# moire_v1_2_plc.net
KiCad netlist of a schematic drawn in EAGLE
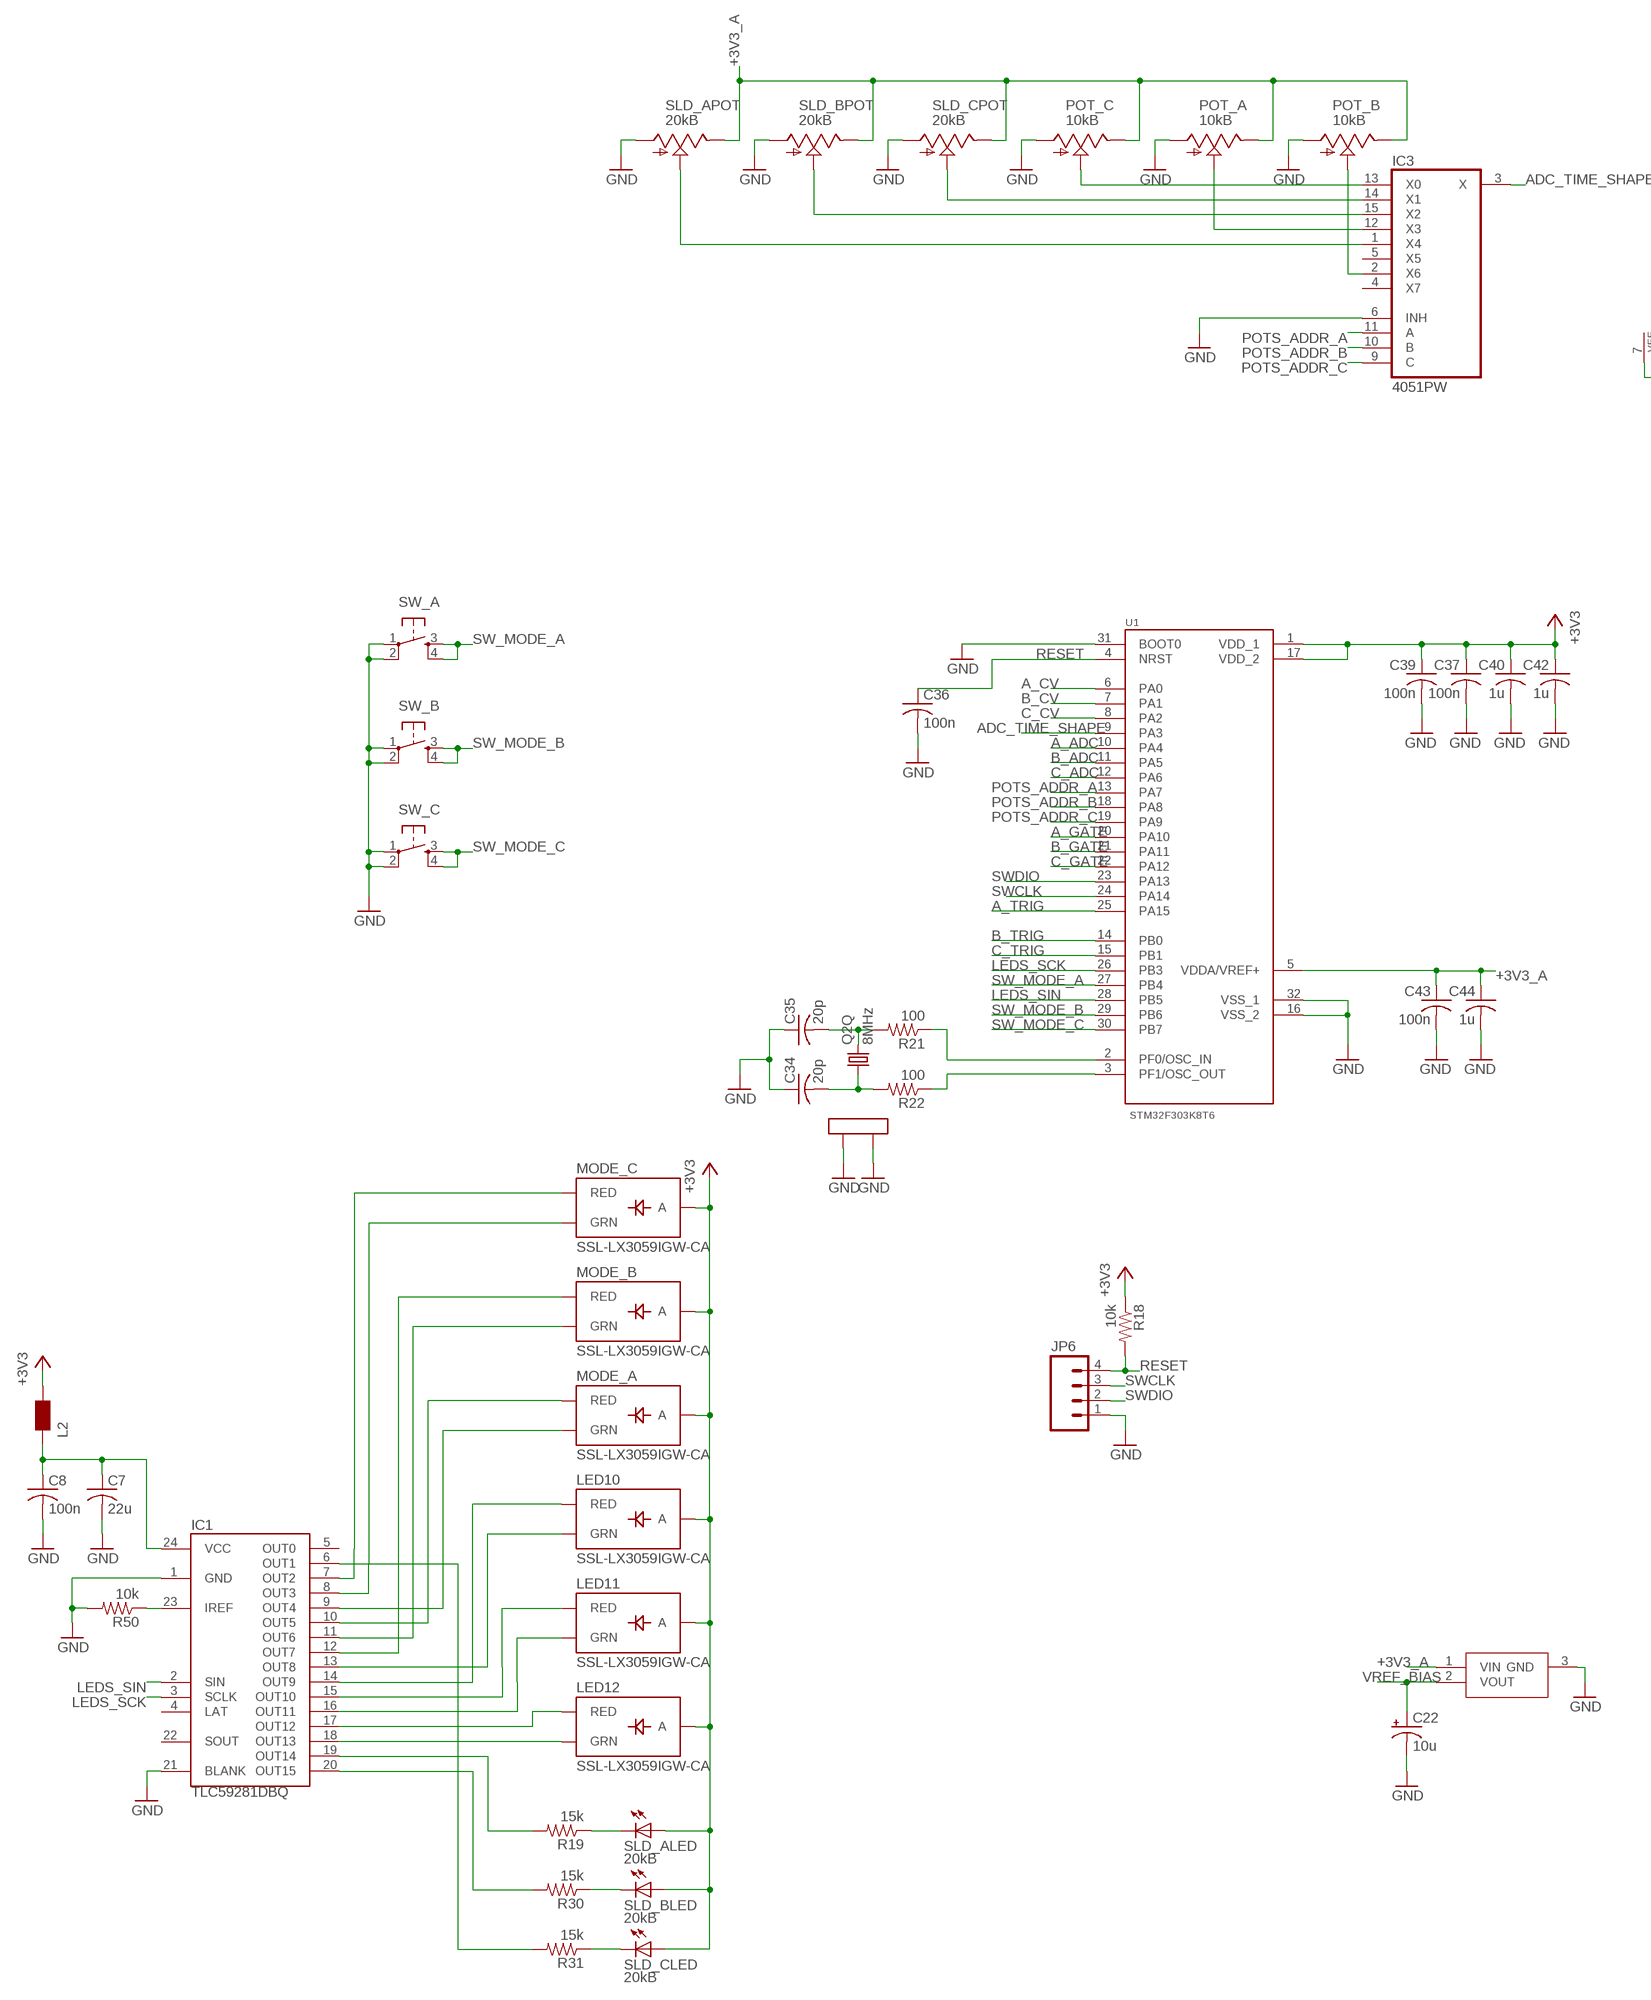
[diagram p0: schematic, sheet 1, part 1 of 2]
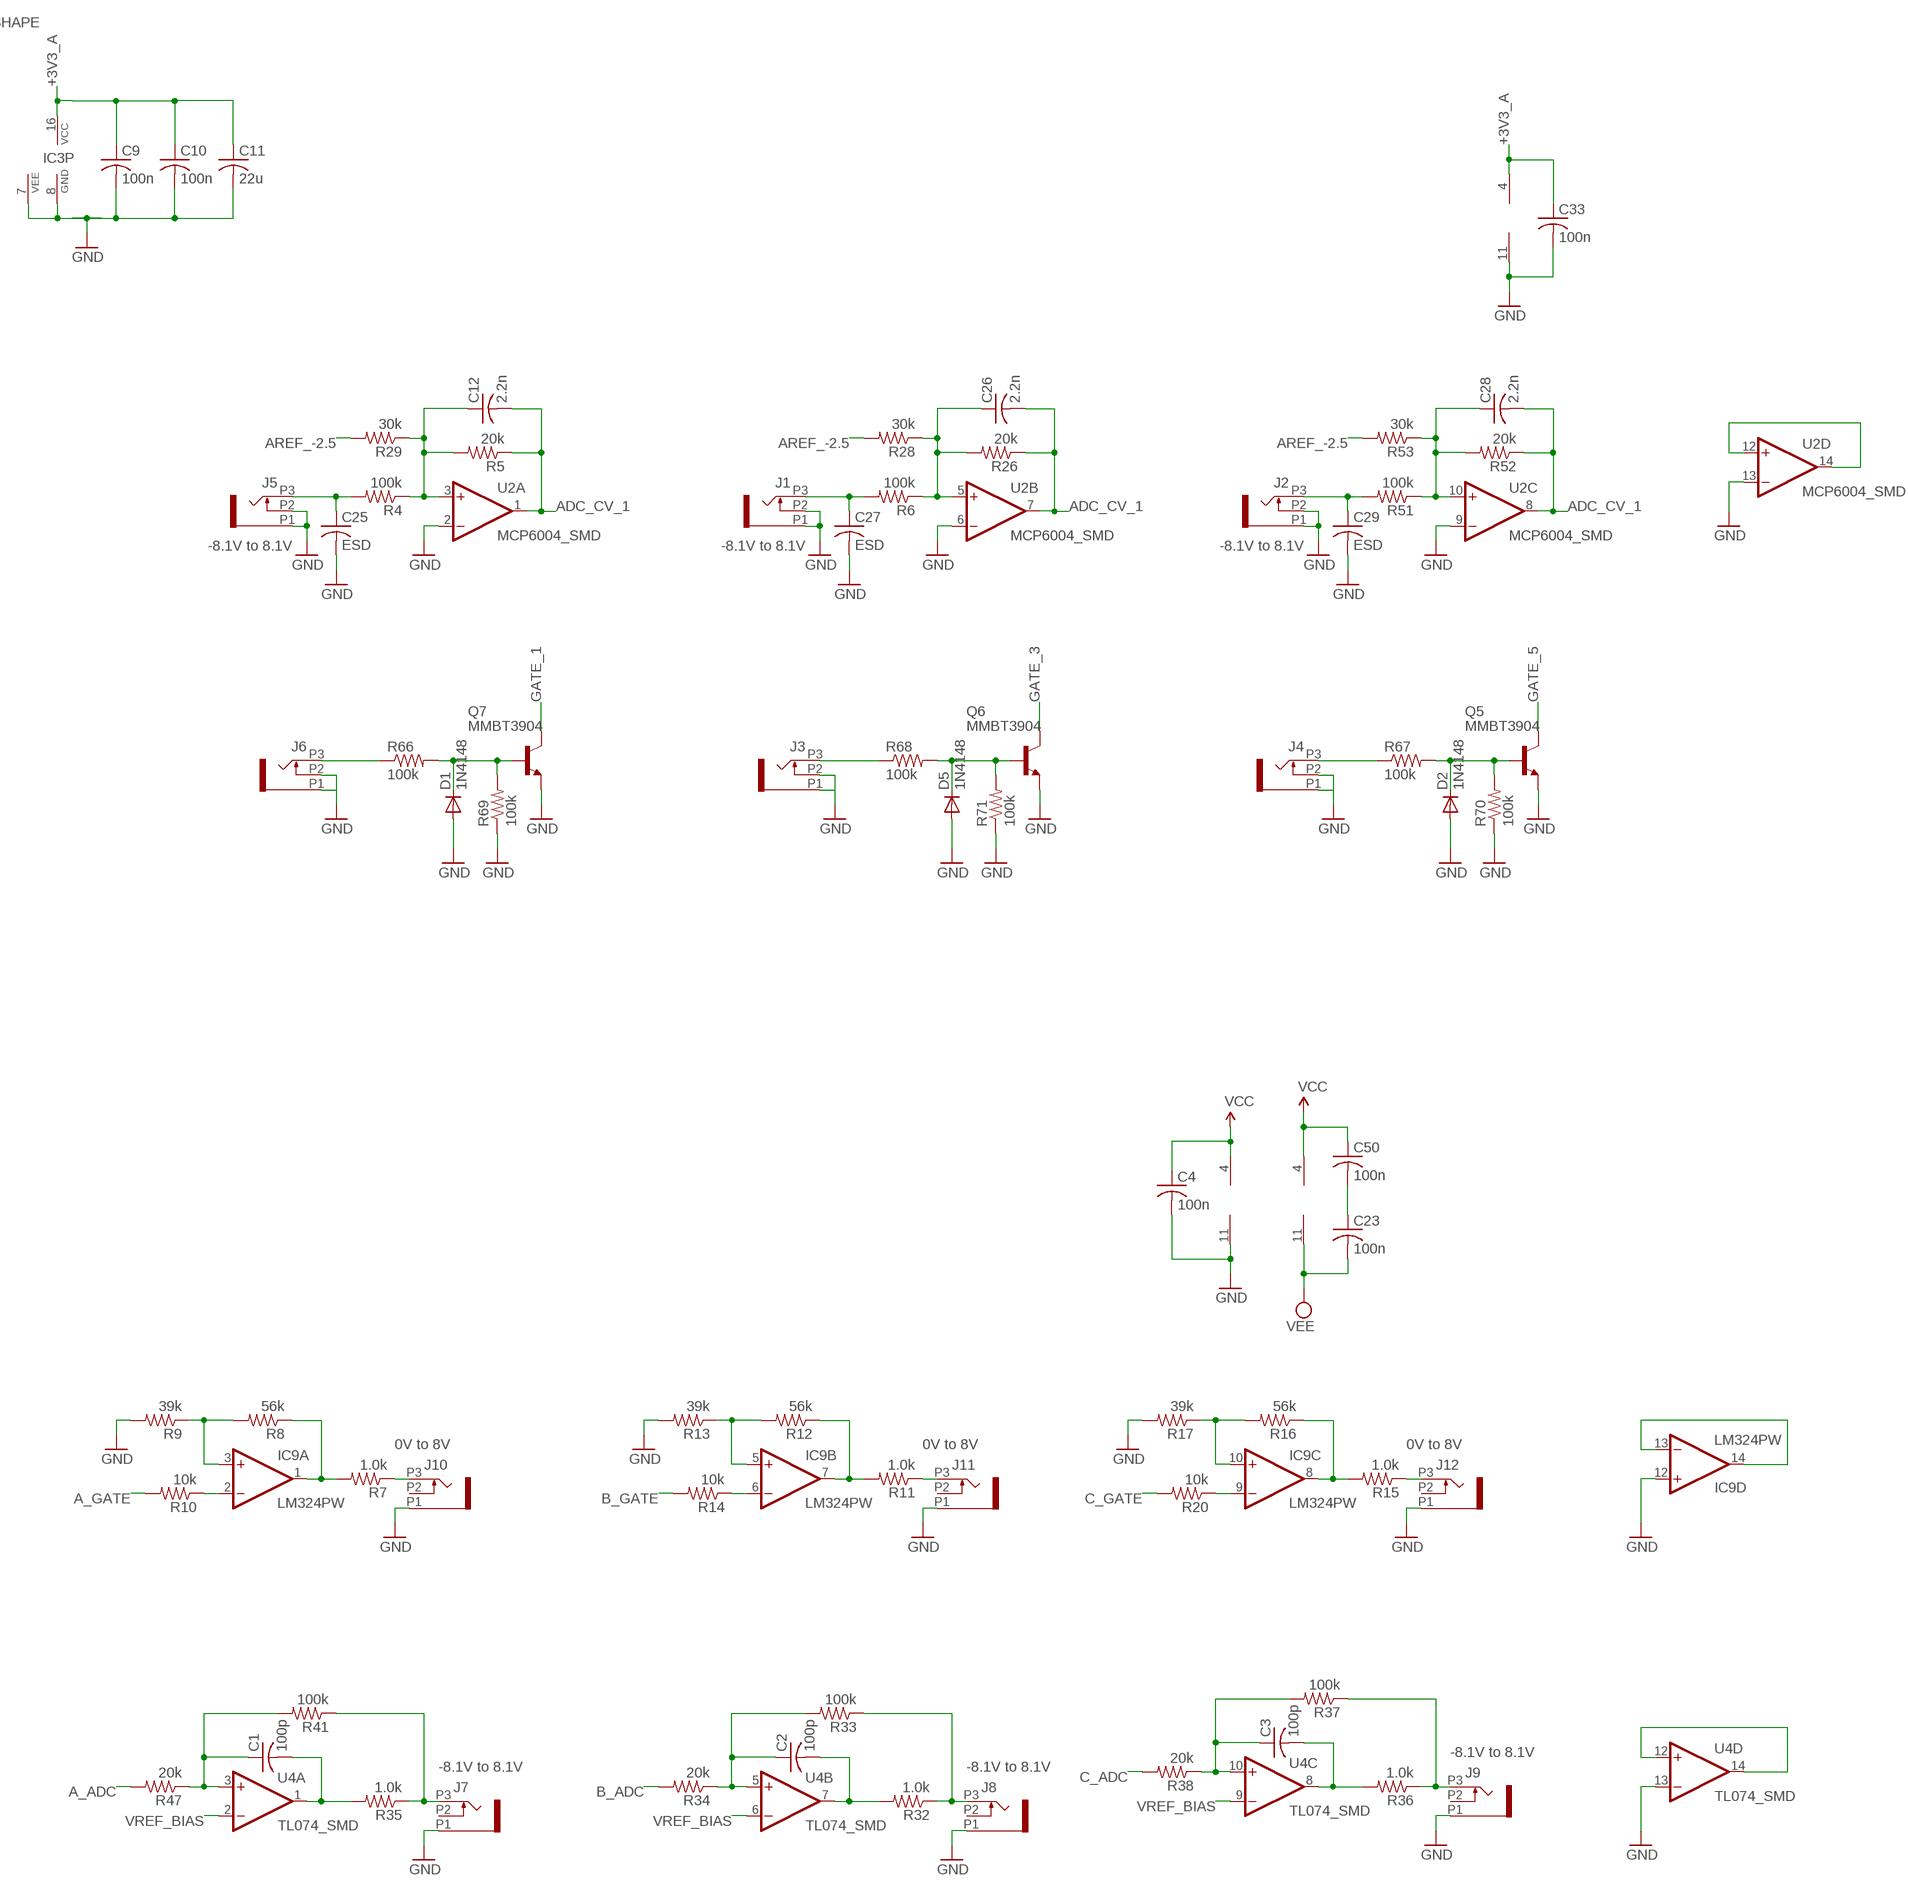
[diagram p1: schematic, sheet 1, part 2 of 2]
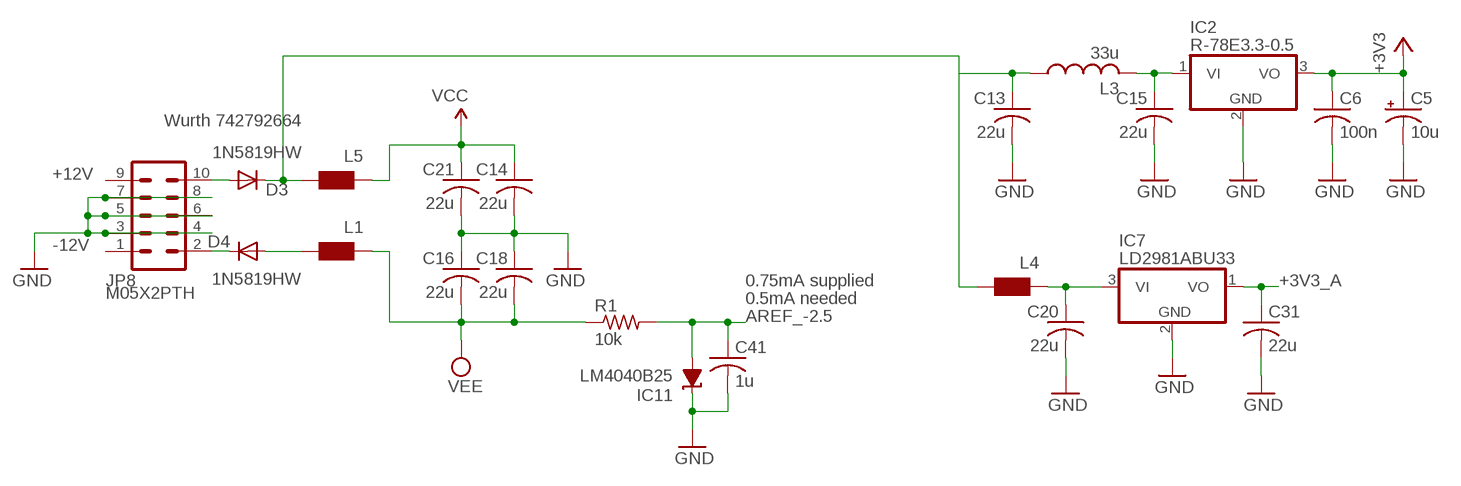
[diagram p2: schematic, sheet 2]

(export (version "E")
  (design (tool "Eeschema 10.0.6"))
  (components
    (comp (ref "C5")
      (value "10u")
      (footprint "eagle-import:PANASONIC_A")
      (libsource (lib "eagle-import") (part "CPOL-USA"))
    )
    (comp (ref "C6")
      (value "100n")
      (footprint "eagle-import:C0402")
      (libsource (lib "eagle-import") (part "C-USC0402"))
    )
    (comp (ref "C13")
      (value "22u")
      (footprint "eagle-import:C1206")
      (libsource (lib "eagle-import") (part "C-USC1206"))
    )
    (comp (ref "C14")
      (value "22u")
      (footprint "eagle-import:C1206")
      (libsource (lib "eagle-import") (part "C-USC1206"))
    )
    (comp (ref "C15")
      (value "22u")
      (footprint "eagle-import:C1206")
      (libsource (lib "eagle-import") (part "C-USC1206"))
    )
    (comp (ref "C16")
      (value "22u")
      (footprint "eagle-import:C1206")
      (libsource (lib "eagle-import") (part "C-USC1206"))
    )
    (comp (ref "C18")
      (value "22u")
      (footprint "eagle-import:C1206")
      (libsource (lib "eagle-import") (part "C-USC1206"))
    )
    (comp (ref "C20")
      (value "22u")
      (footprint "eagle-import:C1206")
      (libsource (lib "eagle-import") (part "C-USC1206"))
    )
    (comp (ref "C21")
      (value "22u")
      (footprint "eagle-import:C1206")
      (libsource (lib "eagle-import") (part "C-USC1206"))
    )
    (comp (ref "C31")
      (value "22u")
      (footprint "eagle-import:C1206")
      (libsource (lib "eagle-import") (part "C-USC1206"))
    )
    (comp (ref "C41")
      (value "1u")
      (footprint "eagle-import:C0402")
      (libsource (lib "eagle-import") (part "C-USC0402"))
    )
    (comp (ref "D3")
      (value "1N5819HW")
      (footprint "eagle-import:SOD123")
      (libsource (lib "eagle-import") (part "DIODE-SOD123"))
    )
    (comp (ref "D4")
      (value "1N5819HW")
      (footprint "eagle-import:SOD123")
      (libsource (lib "eagle-import") (part "DIODE-SOD123"))
    )
    (comp (ref "IC2")
      (value "R-78E3.3-0.5")
      (footprint "eagle-import:WE78")
      (libsource (lib "eagle-import") (part "WE173950378"))
    )
    (comp (ref "IC7")
      (value "LD2981ABU33")
      (footprint "eagle-import:SOT89")
      (libsource (lib "eagle-import") (part "LD2981ABU"))
    )
    (comp (ref "IC11")
      (value "LM4040B25")
      (footprint "eagle-import:DBZ_R-PDSO-G3")
      (libsource (lib "eagle-import") (part "LM4041DBZB12"))
    )
    (comp (ref "JP8")
      (value "M05X2PTH")
      (footprint "eagle-import:2X5-PTH")
      (libsource (lib "eagle-import") (part "M05X2PTH"))
    )
    (comp (ref "L1")
      (value "WE-CBF_0603")
      (footprint "eagle-import:0603")
      (libsource (lib "eagle-import") (part "WE-CBF_0603"))
    )
    (comp (ref "L3")
      (value "33u")
      (footprint "eagle-import:L2012C")
      (libsource (lib "eagle-import") (part "L-USL2012C"))
    )
    (comp (ref "L4")
      (value "WE-CBF_0603")
      (footprint "eagle-import:0603")
      (libsource (lib "eagle-import") (part "WE-CBF_0603"))
    )
    (comp (ref "L5")
      (value "WE-CBF_0603")
      (footprint "eagle-import:0603")
      (libsource (lib "eagle-import") (part "WE-CBF_0603"))
    )
    (comp (ref "R1")
      (value "10k")
      (footprint "eagle-import:R0603")
      (libsource (lib "eagle-import") (part "R-US_R0603"))
    )
    (comp (ref "C1")
      (value "100p")
      (footprint "eagle-import:C0603")
      (libsource (lib "eagle-import") (part "C-USC0603"))
    )
    (comp (ref "C2")
      (value "100p")
      (footprint "eagle-import:C0603")
      (libsource (lib "eagle-import") (part "C-USC0603"))
    )
    (comp (ref "C3")
      (value "100p")
      (footprint "eagle-import:C0603")
      (libsource (lib "eagle-import") (part "C-USC0603"))
    )
    (comp (ref "C4")
      (value "100n")
      (footprint "eagle-import:C0402")
      (libsource (lib "eagle-import") (part "C-USC0402"))
    )
    (comp (ref "C7")
      (value "22u")
      (footprint "eagle-import:C1206")
      (libsource (lib "eagle-import") (part "C-USC1206"))
    )
    (comp (ref "C8")
      (value "100n")
      (footprint "eagle-import:C0603")
      (libsource (lib "eagle-import") (part "C-USC0603"))
    )
    (comp (ref "C9")
      (value "100n")
      (footprint "eagle-import:C0603")
      (libsource (lib "eagle-import") (part "C-USC0603"))
    )
    (comp (ref "C10")
      (value "100n")
      (footprint "eagle-import:C0603")
      (libsource (lib "eagle-import") (part "C-USC0603"))
    )
    (comp (ref "C11")
      (value "22u")
      (footprint "eagle-import:C1206")
      (libsource (lib "eagle-import") (part "C-USC1206"))
    )
    (comp (ref "C12")
      (value "2.2n")
      (footprint "eagle-import:C0402")
      (libsource (lib "eagle-import") (part "C-USC0402"))
    )
    (comp (ref "C22")
      (value "10u")
      (footprint "eagle-import:PANASONIC_A")
      (libsource (lib "eagle-import") (part "CPOL-USA"))
    )
    (comp (ref "C23")
      (value "100n")
      (footprint "eagle-import:C0603")
      (libsource (lib "eagle-import") (part "C-USC0603"))
    )
    (comp (ref "C25")
      (value "ESD")
      (footprint "eagle-import:C0603")
      (libsource (lib "eagle-import") (part "C-USC0603"))
    )
    (comp (ref "C26")
      (value "2.2n")
      (footprint "eagle-import:C0402")
      (libsource (lib "eagle-import") (part "C-USC0402"))
    )
    (comp (ref "C27")
      (value "ESD")
      (footprint "eagle-import:C0603")
      (libsource (lib "eagle-import") (part "C-USC0603"))
    )
    (comp (ref "C28")
      (value "2.2n")
      (footprint "eagle-import:C0402")
      (libsource (lib "eagle-import") (part "C-USC0402"))
    )
    (comp (ref "C29")
      (value "ESD")
      (footprint "eagle-import:C0603")
      (libsource (lib "eagle-import") (part "C-USC0603"))
    )
    (comp (ref "C33")
      (value "100n")
      (footprint "eagle-import:C0603")
      (libsource (lib "eagle-import") (part "C-USC0603"))
    )
    (comp (ref "C34")
      (value "20p")
      (footprint "eagle-import:C0603")
      (libsource (lib "eagle-import") (part "C-USC0603"))
    )
    (comp (ref "C35")
      (value "20p")
      (footprint "eagle-import:C0603")
      (libsource (lib "eagle-import") (part "C-USC0603"))
    )
    (comp (ref "C36")
      (value "100n")
      (footprint "eagle-import:C0603")
      (libsource (lib "eagle-import") (part "C-USC0603"))
    )
    (comp (ref "C37")
      (value "100n")
      (footprint "eagle-import:C0603")
      (libsource (lib "eagle-import") (part "C-USC0603"))
    )
    (comp (ref "C39")
      (value "100n")
      (footprint "eagle-import:C0603")
      (libsource (lib "eagle-import") (part "C-USC0603"))
    )
    (comp (ref "C40")
      (value "1u")
      (footprint "eagle-import:C0603")
      (libsource (lib "eagle-import") (part "C-USC0603"))
    )
    (comp (ref "C42")
      (value "1u")
      (footprint "eagle-import:C0603")
      (libsource (lib "eagle-import") (part "C-USC0603"))
    )
    (comp (ref "C43")
      (value "100n")
      (footprint "eagle-import:C0603")
      (libsource (lib "eagle-import") (part "C-USC0603"))
    )
    (comp (ref "C44")
      (value "1u")
      (footprint "eagle-import:C0603")
      (libsource (lib "eagle-import") (part "C-USC0603"))
    )
    (comp (ref "C50")
      (value "100n")
      (footprint "eagle-import:C0603")
      (libsource (lib "eagle-import") (part "C-USC0603"))
    )
    (comp (ref "D1")
      (value "1N4148")
      (footprint "eagle-import:SOD523")
      (libsource (lib "eagle-import") (part "DIODE-SOD523"))
    )
    (comp (ref "D2")
      (value "1N4148")
      (footprint "eagle-import:SOD523")
      (libsource (lib "eagle-import") (part "DIODE-SOD523"))
    )
    (comp (ref "D5")
      (value "1N4148")
      (footprint "eagle-import:SOD523")
      (libsource (lib "eagle-import") (part "DIODE-SOD523"))
    )
    (comp (ref "IC1")
      (value "TLC59281DBQ")
      (footprint "eagle-import:TSSOP24_0635")
      (libsource (lib "eagle-import") (part "TLC59281DBQ"))
    )
    (comp (ref "IC3")
      (value "4051PW")
      (footprint "eagle-import:TSSOP16_065")
      (libsource (lib "eagle-import") (part "4051PW"))
    )
    (comp (ref "IC9")
      (value "LM324PW")
      (footprint "eagle-import:TSSOP14_065")
      (libsource (lib "eagle-import") (part "TL074PW"))
    )
    (comp (ref "J1")
      (value "PJ301_THONKICONN6")
      (footprint "eagle-import:WQP_PJ_301M6")
      (libsource (lib "eagle-import") (part "PJ301_THONKICONN6"))
    )
    (comp (ref "J2")
      (value "PJ301_THONKICONN6")
      (footprint "eagle-import:WQP_PJ_301M6")
      (libsource (lib "eagle-import") (part "PJ301_THONKICONN6"))
    )
    (comp (ref "J3")
      (value "PJ301_THONKICONN6")
      (footprint "eagle-import:WQP_PJ_301M6")
      (libsource (lib "eagle-import") (part "PJ301_THONKICONN6"))
    )
    (comp (ref "J4")
      (value "PJ301_THONKICONN6")
      (footprint "eagle-import:WQP_PJ_301M6")
      (libsource (lib "eagle-import") (part "PJ301_THONKICONN6"))
    )
    (comp (ref "J5")
      (value "PJ301_THONKICONN6")
      (footprint "eagle-import:WQP_PJ_301M6")
      (libsource (lib "eagle-import") (part "PJ301_THONKICONN6"))
    )
    (comp (ref "J6")
      (value "PJ301_THONKICONN6")
      (footprint "eagle-import:WQP_PJ_301M6")
      (libsource (lib "eagle-import") (part "PJ301_THONKICONN6"))
    )
    (comp (ref "J7")
      (value "PJ301_THONKICONN6")
      (footprint "eagle-import:WQP_PJ_301M6")
      (libsource (lib "eagle-import") (part "PJ301_THONKICONN6"))
    )
    (comp (ref "J8")
      (value "PJ301_THONKICONN6")
      (footprint "eagle-import:WQP_PJ_301M6")
      (libsource (lib "eagle-import") (part "PJ301_THONKICONN6"))
    )
    (comp (ref "J9")
      (value "PJ301_THONKICONN6")
      (footprint "eagle-import:WQP_PJ_301M6")
      (libsource (lib "eagle-import") (part "PJ301_THONKICONN6"))
    )
    (comp (ref "J10")
      (value "PJ301_THONKICONN6")
      (footprint "eagle-import:WQP_PJ_301M6")
      (libsource (lib "eagle-import") (part "PJ301_THONKICONN6"))
    )
    (comp (ref "J11")
      (value "PJ301_THONKICONN6")
      (footprint "eagle-import:WQP_PJ_301M6")
      (libsource (lib "eagle-import") (part "PJ301_THONKICONN6"))
    )
    (comp (ref "J12")
      (value "PJ301_THONKICONN6")
      (footprint "eagle-import:WQP_PJ_301M6")
      (libsource (lib "eagle-import") (part "PJ301_THONKICONN6"))
    )
    (comp (ref "JP6")
      (value "M04PTH")
      (footprint "eagle-import:1X04")
      (libsource (lib "eagle-import") (part "M04PTH"))
    )
    (comp (ref "L2")
      (value "WE-CBF_0603")
      (footprint "eagle-import:0603")
      (libsource (lib "eagle-import") (part "WE-CBF_0603"))
    )
    (comp (ref "LED10")
      (value "SSL-LX3059IGW-CA")
      (footprint "eagle-import:LED-BICOLOR-THROUGHHOLE-LUMEX")
      (libsource (lib "eagle-import") (part "LED-BICOLOR-THROUGHHOLE-CA"))
    )
    (comp (ref "LED11")
      (value "SSL-LX3059IGW-CA")
      (footprint "eagle-import:LED-BICOLOR-THROUGHHOLE-LUMEX")
      (libsource (lib "eagle-import") (part "LED-BICOLOR-THROUGHHOLE-CA"))
    )
    (comp (ref "LED12")
      (value "SSL-LX3059IGW-CA")
      (footprint "eagle-import:LED-BICOLOR-THROUGHHOLE-LUMEX")
      (libsource (lib "eagle-import") (part "LED-BICOLOR-THROUGHHOLE-CA"))
    )
    (comp (ref "MODE_A")
      (value "SSL-LX3059IGW-CA")
      (footprint "eagle-import:LED-BICOLOR-THROUGHHOLE-LUMEX")
      (libsource (lib "eagle-import") (part "LED-BICOLOR-THROUGHHOLE-CA"))
    )
    (comp (ref "MODE_B")
      (value "SSL-LX3059IGW-CA")
      (footprint "eagle-import:LED-BICOLOR-THROUGHHOLE-LUMEX")
      (libsource (lib "eagle-import") (part "LED-BICOLOR-THROUGHHOLE-CA"))
    )
    (comp (ref "MODE_C")
      (value "SSL-LX3059IGW-CA")
      (footprint "eagle-import:LED-BICOLOR-THROUGHHOLE-LUMEX")
      (libsource (lib "eagle-import") (part "LED-BICOLOR-THROUGHHOLE-CA"))
    )
    (comp (ref "POT_A")
      (value "10kB")
      (footprint "eagle-import:ALPS_POT_VERTICAL")
      (libsource (lib "eagle-import") (part "POT_USVERTICAL"))
    )
    (comp (ref "POT_B")
      (value "10kB")
      (footprint "eagle-import:ALPS_POT_VERTICAL")
      (libsource (lib "eagle-import") (part "POT_USVERTICAL"))
    )
    (comp (ref "POT_C")
      (value "10kB")
      (footprint "eagle-import:ALPS_POT_VERTICAL")
      (libsource (lib "eagle-import") (part "POT_USVERTICAL"))
    )
    (comp (ref "Q2")
      (value "8MHz")
      (footprint "eagle-import:CTS406")
      (libsource (lib "eagle-import") (part "CRYSTAL"))
    )
    (comp (ref "Q5")
      (value "MMBT3904")
      (footprint "eagle-import:SOT23-BEC")
      (libsource (lib "eagle-import") (part "-NPN-SOT23-BECMMBT3904LT1"))
    )
    (comp (ref "Q6")
      (value "MMBT3904")
      (footprint "eagle-import:SOT23-BEC")
      (libsource (lib "eagle-import") (part "-NPN-SOT23-BECMMBT3904LT1"))
    )
    (comp (ref "Q7")
      (value "MMBT3904")
      (footprint "eagle-import:SOT23-BEC")
      (libsource (lib "eagle-import") (part "-NPN-SOT23-BECMMBT3904LT1"))
    )
    (comp (ref "R4")
      (value "100k")
      (footprint "eagle-import:R0603")
      (libsource (lib "eagle-import") (part "R-US_R0603"))
    )
    (comp (ref "R5")
      (value "20k")
      (footprint "eagle-import:R0603")
      (libsource (lib "eagle-import") (part "R-US_R0603"))
    )
    (comp (ref "R6")
      (value "100k")
      (footprint "eagle-import:R0603")
      (libsource (lib "eagle-import") (part "R-US_R0603"))
    )
    (comp (ref "R7")
      (value "1.0k")
      (footprint "eagle-import:R0603")
      (libsource (lib "eagle-import") (part "R-US_R0603"))
    )
    (comp (ref "R8")
      (value "56k")
      (footprint "eagle-import:R0603")
      (libsource (lib "eagle-import") (part "R-US_R0603"))
    )
    (comp (ref "R9")
      (value "39k")
      (footprint "eagle-import:R0603")
      (libsource (lib "eagle-import") (part "R-US_R0603"))
    )
    (comp (ref "R10")
      (value "10k")
      (footprint "eagle-import:R0603")
      (libsource (lib "eagle-import") (part "R-US_R0603"))
    )
    (comp (ref "R11")
      (value "1.0k")
      (footprint "eagle-import:R0603")
      (libsource (lib "eagle-import") (part "R-US_R0603"))
    )
    (comp (ref "R12")
      (value "56k")
      (footprint "eagle-import:R0603")
      (libsource (lib "eagle-import") (part "R-US_R0603"))
    )
    (comp (ref "R13")
      (value "39k")
      (footprint "eagle-import:R0603")
      (libsource (lib "eagle-import") (part "R-US_R0603"))
    )
    (comp (ref "R14")
      (value "10k")
      (footprint "eagle-import:R0603")
      (libsource (lib "eagle-import") (part "R-US_R0603"))
    )
    (comp (ref "R15")
      (value "1.0k")
      (footprint "eagle-import:R0603")
      (libsource (lib "eagle-import") (part "R-US_R0603"))
    )
    (comp (ref "R16")
      (value "56k")
      (footprint "eagle-import:R0603")
      (libsource (lib "eagle-import") (part "R-US_R0603"))
    )
    (comp (ref "R17")
      (value "39k")
      (footprint "eagle-import:R0603")
      (libsource (lib "eagle-import") (part "R-US_R0603"))
    )
    (comp (ref "R18")
      (value "10k")
      (footprint "eagle-import:R0603")
      (libsource (lib "eagle-import") (part "R-US_R0603"))
    )
    (comp (ref "R19")
      (value "15k")
      (footprint "eagle-import:R0603")
      (libsource (lib "eagle-import") (part "R-US_R0603"))
    )
    (comp (ref "R20")
      (value "10k")
      (footprint "eagle-import:R0603")
      (libsource (lib "eagle-import") (part "R-US_R0603"))
    )
    (comp (ref "R21")
      (value "100")
      (footprint "eagle-import:R0603")
      (libsource (lib "eagle-import") (part "R-US_R0603"))
    )
    (comp (ref "R22")
      (value "100")
      (footprint "eagle-import:R0603")
      (libsource (lib "eagle-import") (part "R-US_R0603"))
    )
    (comp (ref "R26")
      (value "20k")
      (footprint "eagle-import:R0603")
      (libsource (lib "eagle-import") (part "R-US_R0603"))
    )
    (comp (ref "R28")
      (value "30k")
      (footprint "eagle-import:R0603")
      (libsource (lib "eagle-import") (part "R-US_R0603"))
    )
    (comp (ref "R29")
      (value "30k")
      (footprint "eagle-import:R0603")
      (libsource (lib "eagle-import") (part "R-US_R0603"))
    )
    (comp (ref "R30")
      (value "15k")
      (footprint "eagle-import:R0603")
      (libsource (lib "eagle-import") (part "R-US_R0603"))
    )
    (comp (ref "R31")
      (value "15k")
      (footprint "eagle-import:R0603")
      (libsource (lib "eagle-import") (part "R-US_R0603"))
    )
    (comp (ref "R32")
      (value "1.0k")
      (footprint "eagle-import:R0603")
      (libsource (lib "eagle-import") (part "R-US_R0603"))
    )
    (comp (ref "R33")
      (value "100k")
      (footprint "eagle-import:R0603")
      (libsource (lib "eagle-import") (part "R-US_R0603"))
    )
    (comp (ref "R34")
      (value "20k")
      (footprint "eagle-import:R0603")
      (libsource (lib "eagle-import") (part "R-US_R0603"))
    )
    (comp (ref "R35")
      (value "1.0k")
      (footprint "eagle-import:R0603")
      (libsource (lib "eagle-import") (part "R-US_R0603"))
    )
    (comp (ref "R36")
      (value "1.0k")
      (footprint "eagle-import:R0603")
      (libsource (lib "eagle-import") (part "R-US_R0603"))
    )
    (comp (ref "R37")
      (value "100k")
      (footprint "eagle-import:R0603")
      (libsource (lib "eagle-import") (part "R-US_R0603"))
    )
    (comp (ref "R38")
      (value "20k")
      (footprint "eagle-import:R0603")
      (libsource (lib "eagle-import") (part "R-US_R0603"))
    )
    (comp (ref "R41")
      (value "100k")
      (footprint "eagle-import:R0603")
      (libsource (lib "eagle-import") (part "R-US_R0603"))
    )
    (comp (ref "R47")
      (value "20k")
      (footprint "eagle-import:R0603")
      (libsource (lib "eagle-import") (part "R-US_R0603"))
    )
    (comp (ref "R50")
      (value "10k")
      (footprint "eagle-import:R0603")
      (libsource (lib "eagle-import") (part "R-US_R0603"))
    )
    (comp (ref "R51")
      (value "100k")
      (footprint "eagle-import:R0603")
      (libsource (lib "eagle-import") (part "R-US_R0603"))
    )
    (comp (ref "R52")
      (value "20k")
      (footprint "eagle-import:R0603")
      (libsource (lib "eagle-import") (part "R-US_R0603"))
    )
    (comp (ref "R53")
      (value "30k")
      (footprint "eagle-import:R0603")
      (libsource (lib "eagle-import") (part "R-US_R0603"))
    )
    (comp (ref "R66")
      (value "100k")
      (footprint "eagle-import:R0603")
      (libsource (lib "eagle-import") (part "R-US_R0603"))
    )
    (comp (ref "R67")
      (value "100k")
      (footprint "eagle-import:R0603")
      (libsource (lib "eagle-import") (part "R-US_R0603"))
    )
    (comp (ref "R68")
      (value "100k")
      (footprint "eagle-import:R0603")
      (libsource (lib "eagle-import") (part "R-US_R0603"))
    )
    (comp (ref "R69")
      (value "100k")
      (footprint "eagle-import:R0603")
      (libsource (lib "eagle-import") (part "R-US_R0603"))
    )
    (comp (ref "R70")
      (value "100k")
      (footprint "eagle-import:R0603")
      (libsource (lib "eagle-import") (part "R-US_R0603"))
    )
    (comp (ref "R71")
      (value "100k")
      (footprint "eagle-import:R0603")
      (libsource (lib "eagle-import") (part "R-US_R0603"))
    )
    (comp (ref "SLD_A")
      (value "20kB")
      (footprint "eagle-import:BOURNS_SLIDER")
      (libsource (lib "eagle-import") (part "BOURNS_SLIDER"))
    )
    (comp (ref "SLD_B")
      (value "20kB")
      (footprint "eagle-import:BOURNS_SLIDER")
      (libsource (lib "eagle-import") (part "BOURNS_SLIDER"))
    )
    (comp (ref "SLD_C")
      (value "20kB")
      (footprint "eagle-import:BOURNS_SLIDER")
      (libsource (lib "eagle-import") (part "BOURNS_SLIDER"))
    )
    (comp (ref "SW_A")
      (value "TAC_SWITCHPTH")
      (footprint "eagle-import:TACTILE-PTH")
      (libsource (lib "eagle-import") (part "TAC_SWITCHPTH"))
    )
    (comp (ref "SW_B")
      (value "TAC_SWITCHPTH")
      (footprint "eagle-import:TACTILE-PTH")
      (libsource (lib "eagle-import") (part "TAC_SWITCHPTH"))
    )
    (comp (ref "SW_C")
      (value "TAC_SWITCHPTH")
      (footprint "eagle-import:TACTILE-PTH")
      (libsource (lib "eagle-import") (part "TAC_SWITCHPTH"))
    )
    (comp (ref "U$1")
      (value "VREF 1.5V")
      (footprint "eagle-import:SOT-23-3")
      (libsource (lib "eagle-import") (part "ISL21010"))
    )
    (comp (ref "U1")
      (value "STM32F303K8T6")
      (footprint "eagle-import:QFP80P900X900X160-32N")
      (fields (field (name "MF") "STMicroelectronics"))
      (libsource (lib "eagle-import") (part "STM32F303K8T6"))
    )
    (comp (ref "U2")
      (value "MCP6004_SMD")
      (footprint "eagle-import:SO14")
      (libsource (lib "eagle-import") (part "MCP6004_SMD"))
    )
    (comp (ref "U4")
      (value "TL074_SMD")
      (footprint "eagle-import:SO14")
      (libsource (lib "eagle-import") (part "TL074_SMD"))
    )
  )
  (nets
    (net (code "1") (name "+3V3") (class "Default")
      (node (ref "C37") (pin "1") (pinfunction "1_1") (pintype "passive"))
      (node (ref "C39") (pin "1") (pinfunction "1_1") (pintype "passive"))
      (node (ref "C40") (pin "1") (pinfunction "1_1") (pintype "passive"))
      (node (ref "C42") (pin "1") (pinfunction "1_1") (pintype "passive"))
      (node (ref "C5") (pin "+") (pinfunction "+_+") (pintype "passive"))
      (node (ref "C6") (pin "1") (pinfunction "1_1") (pintype "passive"))
      (node (ref "IC2") (pin "3") (pinfunction "VO_3") (pintype "passive"))
      (node (ref "L2") (pin "2") (pinfunction "2_2") (pintype "passive"))
      (node (ref "LED10") (pin "A") (pinfunction "A_A") (pintype "bidirectional"))
      (node (ref "LED11") (pin "A") (pinfunction "A_A") (pintype "bidirectional"))
      (node (ref "LED12") (pin "A") (pinfunction "A_A") (pintype "bidirectional"))
      (node (ref "MODE_A") (pin "A") (pinfunction "A_A") (pintype "bidirectional"))
      (node (ref "MODE_B") (pin "A") (pinfunction "A_A") (pintype "bidirectional"))
      (node (ref "MODE_C") (pin "A") (pinfunction "A_A") (pintype "bidirectional"))
      (node (ref "R18") (pin "1") (pinfunction "1_1") (pintype "passive"))
      (node (ref "SLD_A") (pin "B") (pinfunction "A_B") (pintype "passive"))
      (node (ref "SLD_B") (pin "B") (pinfunction "A_B") (pintype "passive"))
      (node (ref "SLD_C") (pin "B") (pinfunction "A_B") (pintype "passive"))
      (node (ref "U1") (pin "1") (pinfunction "VDD_1_1") (pintype "power_in"))
      (node (ref "U1") (pin "17") (pinfunction "VDD_2_17") (pintype "power_in"))
    )
    (net (code "2") (name "+3V3_A") (class "Default")
      (node (ref "C10") (pin "1") (pinfunction "1_1") (pintype "passive"))
      (node (ref "C11") (pin "1") (pinfunction "1_1") (pintype "passive"))
      (node (ref "C31") (pin "1") (pinfunction "1_1") (pintype "passive"))
      (node (ref "C33") (pin "1") (pinfunction "1_1") (pintype "passive"))
      (node (ref "C43") (pin "1") (pinfunction "1_1") (pintype "passive"))
      (node (ref "C44") (pin "1") (pinfunction "1_1") (pintype "passive"))
      (node (ref "C9") (pin "1") (pinfunction "1_1") (pintype "passive"))
      (node (ref "IC3") (pin "16") (pinfunction "VCC_16") (pintype "power_in"))
      (node (ref "IC7") (pin "1") (pinfunction "VO_1") (pintype "passive"))
      (node (ref "POT_A") (pin "P$1") (pinfunction "E_P$1") (pintype "passive"))
      (node (ref "POT_B") (pin "P$1") (pinfunction "E_P$1") (pintype "passive"))
      (node (ref "POT_C") (pin "P$1") (pinfunction "E_P$1") (pintype "passive"))
      (node (ref "SLD_A") (pin "3") (pinfunction "E_3") (pintype "passive"))
      (node (ref "SLD_B") (pin "3") (pinfunction "E_3") (pintype "passive"))
      (node (ref "SLD_C") (pin "3") (pinfunction "E_3") (pintype "passive"))
      (node (ref "U$1") (pin "1") (pinfunction "VIN_1") (pintype "input"))
      (node (ref "U1") (pin "5") (pinfunction "VDDA/VREF+_5") (pintype "power_in"))
      (node (ref "U2") (pin "4") (pinfunction "V+_4") (pintype "power_in"))
    )
    (net (code "3") (name "+12V") (class "Default")
      (node (ref "D3") (pin "A") (pinfunction "A_A") (pintype "passive"))
      (node (ref "JP8") (pin "10") (pinfunction "10_10") (pintype "passive"))
      (node (ref "JP8") (pin "9") (pinfunction "9_9") (pintype "passive"))
    )
    (net (code "4") (name "-12V") (class "Default")
      (node (ref "D4") (pin "C") (pinfunction "C_C") (pintype "passive"))
      (node (ref "JP8") (pin "1") (pinfunction "1_1") (pintype "passive"))
      (node (ref "JP8") (pin "2") (pinfunction "2_2") (pintype "passive"))
    )
    (net (code "5") (name "ADC_CV_1") (class "Default")
      (node (ref "C12") (pin "2") (pinfunction "2_2") (pintype "passive"))
      (node (ref "C26") (pin "2") (pinfunction "2_2") (pintype "passive"))
      (node (ref "C28") (pin "2") (pinfunction "2_2") (pintype "passive"))
      (node (ref "R26") (pin "1") (pinfunction "1_1") (pintype "passive"))
      (node (ref "R5") (pin "1") (pinfunction "1_1") (pintype "passive"))
      (node (ref "R52") (pin "1") (pinfunction "1_1") (pintype "passive"))
      (node (ref "U2") (pin "1") (pinfunction "OUT_1") (pintype "output"))
      (node (ref "U2") (pin "7") (pinfunction "OUT_7") (pintype "output"))
      (node (ref "U2") (pin "8") (pinfunction "OUT_8") (pintype "output"))
    )
    (net (code "6") (name "ADC_TIME_SHAPE") (class "Default")
      (node (ref "IC3") (pin "3") (pinfunction "X_3") (pintype "bidirectional"))
      (node (ref "U1") (pin "9") (pinfunction "PA3_9") (pintype "bidirectional"))
    )
    (net (code "7") (name "AREF_-2.5") (class "Default")
      (node (ref "C41") (pin "1") (pinfunction "1_1") (pintype "passive"))
      (node (ref "IC11") (pin "2") (pinfunction "A_2") (pintype "passive"))
      (node (ref "R1") (pin "2") (pinfunction "2_2") (pintype "passive"))
      (node (ref "R28") (pin "2") (pinfunction "2_2") (pintype "passive"))
      (node (ref "R29") (pin "2") (pinfunction "2_2") (pintype "passive"))
      (node (ref "R53") (pin "2") (pinfunction "2_2") (pintype "passive"))
    )
    (net (code "8") (name "A_ADC") (class "Default")
      (node (ref "R47") (pin "2") (pinfunction "2_2") (pintype "passive"))
      (node (ref "U1") (pin "10") (pinfunction "PA4_10") (pintype "bidirectional"))
    )
    (net (code "9") (name "A_CV") (class "Default")
      (node (ref "U1") (pin "6") (pinfunction "PA0_6") (pintype "bidirectional"))
    )
    (net (code "10") (name "A_GATE") (class "Default")
      (node (ref "R10") (pin "2") (pinfunction "2_2") (pintype "passive"))
      (node (ref "U1") (pin "20") (pinfunction "PA10_20") (pintype "bidirectional"))
    )
    (net (code "11") (name "A_TRIG") (class "Default")
      (node (ref "U1") (pin "25") (pinfunction "PA15_25") (pintype "bidirectional"))
    )
    (net (code "12") (name "B_ADC") (class "Default")
      (node (ref "R34") (pin "2") (pinfunction "2_2") (pintype "passive"))
      (node (ref "U1") (pin "11") (pinfunction "PA5_11") (pintype "bidirectional"))
    )
    (net (code "13") (name "B_CV") (class "Default")
      (node (ref "U1") (pin "7") (pinfunction "PA1_7") (pintype "bidirectional"))
    )
    (net (code "14") (name "B_GATE") (class "Default")
      (node (ref "R14") (pin "2") (pinfunction "2_2") (pintype "passive"))
      (node (ref "U1") (pin "21") (pinfunction "PA11_21") (pintype "bidirectional"))
    )
    (net (code "15") (name "B_TRIG") (class "Default")
      (node (ref "U1") (pin "14") (pinfunction "PB0_14") (pintype "bidirectional"))
    )
    (net (code "16") (name "C_ADC") (class "Default")
      (node (ref "R38") (pin "2") (pinfunction "2_2") (pintype "passive"))
      (node (ref "U1") (pin "12") (pinfunction "PA6_12") (pintype "bidirectional"))
    )
    (net (code "17") (name "C_CV") (class "Default")
      (node (ref "U1") (pin "8") (pinfunction "PA2_8") (pintype "bidirectional"))
    )
    (net (code "18") (name "C_GATE") (class "Default")
      (node (ref "R20") (pin "2") (pinfunction "2_2") (pintype "passive"))
      (node (ref "U1") (pin "22") (pinfunction "PA12_22") (pintype "bidirectional"))
    )
    (net (code "19") (name "C_TRIG") (class "Default")
      (node (ref "U1") (pin "15") (pinfunction "PB1_15") (pintype "bidirectional"))
    )
    (net (code "20") (name "GATE_1") (class "Default")
      (node (ref "Q7") (pin "C") (pinfunction "C_C") (pintype "passive"))
    )
    (net (code "21") (name "GATE_3") (class "Default")
      (node (ref "Q6") (pin "C") (pinfunction "C_C") (pintype "passive"))
    )
    (net (code "22") (name "GATE_5") (class "Default")
      (node (ref "Q5") (pin "C") (pinfunction "C_C") (pintype "passive"))
    )
    (net (code "23") (name "GND") (class "Default")
      (node (ref "C10") (pin "2") (pinfunction "2_2") (pintype "passive"))
      (node (ref "C11") (pin "2") (pinfunction "2_2") (pintype "passive"))
      (node (ref "C13") (pin "2") (pinfunction "2_2") (pintype "passive"))
      (node (ref "C14") (pin "2") (pinfunction "2_2") (pintype "passive"))
      (node (ref "C15") (pin "2") (pinfunction "2_2") (pintype "passive"))
      (node (ref "C16") (pin "1") (pinfunction "1_1") (pintype "passive"))
      (node (ref "C18") (pin "1") (pinfunction "1_1") (pintype "passive"))
      (node (ref "C20") (pin "2") (pinfunction "2_2") (pintype "passive"))
      (node (ref "C21") (pin "2") (pinfunction "2_2") (pintype "passive"))
      (node (ref "C22") (pin "-") (pinfunction "-_-") (pintype "passive"))
      (node (ref "C25") (pin "2") (pinfunction "2_2") (pintype "passive"))
      (node (ref "C27") (pin "2") (pinfunction "2_2") (pintype "passive"))
      (node (ref "C29") (pin "2") (pinfunction "2_2") (pintype "passive"))
      (node (ref "C31") (pin "2") (pinfunction "2_2") (pintype "passive"))
      (node (ref "C33") (pin "2") (pinfunction "2_2") (pintype "passive"))
      (node (ref "C34") (pin "1") (pinfunction "1_1") (pintype "passive"))
      (node (ref "C35") (pin "1") (pinfunction "1_1") (pintype "passive"))
      (node (ref "C36") (pin "2") (pinfunction "2_2") (pintype "passive"))
      (node (ref "C37") (pin "2") (pinfunction "2_2") (pintype "passive"))
      (node (ref "C39") (pin "2") (pinfunction "2_2") (pintype "passive"))
      (node (ref "C4") (pin "2") (pinfunction "2_2") (pintype "passive"))
      (node (ref "C40") (pin "2") (pinfunction "2_2") (pintype "passive"))
      (node (ref "C41") (pin "2") (pinfunction "2_2") (pintype "passive"))
      (node (ref "C42") (pin "2") (pinfunction "2_2") (pintype "passive"))
      (node (ref "C43") (pin "2") (pinfunction "2_2") (pintype "passive"))
      (node (ref "C44") (pin "2") (pinfunction "2_2") (pintype "passive"))
      (node (ref "C5") (pin "-") (pinfunction "-_-") (pintype "passive"))
      (node (ref "C6") (pin "2") (pinfunction "2_2") (pintype "passive"))
      (node (ref "C7") (pin "2") (pinfunction "2_2") (pintype "passive"))
      (node (ref "C8") (pin "2") (pinfunction "2_2") (pintype "passive"))
      (node (ref "C9") (pin "2") (pinfunction "2_2") (pintype "passive"))
      (node (ref "D1") (pin "A") (pinfunction "A_A") (pintype "passive"))
      (node (ref "D2") (pin "A") (pinfunction "A_A") (pintype "passive"))
      (node (ref "D5") (pin "A") (pinfunction "A_A") (pintype "passive"))
      (node (ref "IC1") (pin "1") (pinfunction "GND_1") (pintype "bidirectional"))
      (node (ref "IC1") (pin "21") (pinfunction "BLANK_21") (pintype "bidirectional"))
      (node (ref "IC11") (pin "1") (pinfunction "C_1") (pintype "passive"))
      (node (ref "IC2") (pin "2") (pinfunction "GND_2") (pintype "passive"))
      (node (ref "IC3") (pin "6") (pinfunction "INH_6") (pintype "input"))
      (node (ref "IC3") (pin "7") (pinfunction "VEE_7") (pintype "power_in"))
      (node (ref "IC3") (pin "8") (pinfunction "GND_8") (pintype "power_in"))
      (node (ref "IC7") (pin "2") (pinfunction "GND_2") (pintype "passive"))
      (node (ref "IC9") (pin "11") (pinfunction "V-_11") (pintype "power_in"))
      (node (ref "IC9") (pin "12") (pinfunction "+IN_12") (pintype "input"))
      (node (ref "J1") (pin "P1") (pinfunction "1_P1") (pintype "passive"))
      (node (ref "J1") (pin "P2") (pinfunction "2_P2") (pintype "passive"))
      (node (ref "J10") (pin "P1") (pinfunction "1_P1") (pintype "passive"))
      (node (ref "J11") (pin "P1") (pinfunction "1_P1") (pintype "passive"))
      (node (ref "J12") (pin "P1") (pinfunction "1_P1") (pintype "passive"))
      (node (ref "J2") (pin "P1") (pinfunction "1_P1") (pintype "passive"))
      (node (ref "J2") (pin "P2") (pinfunction "2_P2") (pintype "passive"))
      (node (ref "J3") (pin "P1") (pinfunction "1_P1") (pintype "passive"))
      (node (ref "J3") (pin "P2") (pinfunction "2_P2") (pintype "passive"))
      (node (ref "J4") (pin "P1") (pinfunction "1_P1") (pintype "passive"))
      (node (ref "J4") (pin "P2") (pinfunction "2_P2") (pintype "passive"))
      (node (ref "J5") (pin "P1") (pinfunction "1_P1") (pintype "passive"))
      (node (ref "J5") (pin "P2") (pinfunction "2_P2") (pintype "passive"))
      (node (ref "J6") (pin "P1") (pinfunction "1_P1") (pintype "passive"))
      (node (ref "J6") (pin "P2") (pinfunction "2_P2") (pintype "passive"))
      (node (ref "J7") (pin "P1") (pinfunction "1_P1") (pintype "passive"))
      (node (ref "J8") (pin "P1") (pinfunction "1_P1") (pintype "passive"))
      (node (ref "J9") (pin "P1") (pinfunction "1_P1") (pintype "passive"))
      (node (ref "JP6") (pin "1") (pinfunction "1_1") (pintype "passive"))
      (node (ref "JP8") (pin "3") (pinfunction "3_3") (pintype "passive"))
      (node (ref "JP8") (pin "4") (pinfunction "4_4") (pintype "passive"))
      (node (ref "JP8") (pin "5") (pinfunction "5_5") (pintype "passive"))
      (node (ref "JP8") (pin "6") (pinfunction "6_6") (pintype "passive"))
      (node (ref "JP8") (pin "7") (pinfunction "7_7") (pintype "passive"))
      (node (ref "JP8") (pin "8") (pinfunction "8_8") (pintype "passive"))
      (node (ref "POT_A") (pin "P$3") (pinfunction "A_P$3") (pintype "passive"))
      (node (ref "POT_B") (pin "P$3") (pinfunction "A_P$3") (pintype "passive"))
      (node (ref "POT_C") (pin "P$3") (pinfunction "A_P$3") (pintype "passive"))
      (node (ref "Q2") (pin "2") (pinfunction "LID1_2") (pintype "power_in"))
      (node (ref "Q2") (pin "4") (pinfunction "LID2_4") (pintype "power_in"))
      (node (ref "Q5") (pin "E") (pinfunction "E_E") (pintype "passive"))
      (node (ref "Q6") (pin "E") (pinfunction "E_E") (pintype "passive"))
      (node (ref "Q7") (pin "E") (pinfunction "E_E") (pintype "passive"))
      (node (ref "R13") (pin "2") (pinfunction "2_2") (pintype "passive"))
      (node (ref "R17") (pin "2") (pinfunction "2_2") (pintype "passive"))
      (node (ref "R50") (pin "2") (pinfunction "2_2") (pintype "passive"))
      (node (ref "R69") (pin "1") (pinfunction "1_1") (pintype "passive"))
      (node (ref "R70") (pin "1") (pinfunction "1_1") (pintype "passive"))
      (node (ref "R71") (pin "1") (pinfunction "1_1") (pintype "passive"))
      (node (ref "R9") (pin "2") (pinfunction "2_2") (pintype "passive"))
      (node (ref "SLD_A") (pin "1") (pinfunction "A_1") (pintype "passive"))
      (node (ref "SLD_B") (pin "1") (pinfunction "A_1") (pintype "passive"))
      (node (ref "SLD_C") (pin "1") (pinfunction "A_1") (pintype "passive"))
      (node (ref "SW_A") (pin "1") (pinfunction "1_1") (pintype "passive"))
      (node (ref "SW_A") (pin "2") (pinfunction "2_2") (pintype "passive"))
      (node (ref "SW_B") (pin "1") (pinfunction "1_1") (pintype "passive"))
      (node (ref "SW_B") (pin "2") (pinfunction "2_2") (pintype "passive"))
      (node (ref "SW_C") (pin "1") (pinfunction "1_1") (pintype "passive"))
      (node (ref "SW_C") (pin "2") (pinfunction "2_2") (pintype "passive"))
      (node (ref "U$1") (pin "3") (pinfunction "GND_3") (pintype "power_in"))
      (node (ref "U1") (pin "16") (pinfunction "VSS_2_16") (pintype "power_in"))
      (node (ref "U1") (pin "31") (pinfunction "BOOT0_31") (pintype "input"))
      (node (ref "U1") (pin "32") (pinfunction "VSS_1_32") (pintype "power_in"))
      (node (ref "U2") (pin "11") (pinfunction "V-_11") (pintype "power_in"))
      (node (ref "U2") (pin "13") (pinfunction "-IN_13") (pintype "input"))
      (node (ref "U2") (pin "2") (pinfunction "-IN_2") (pintype "input"))
      (node (ref "U2") (pin "6") (pinfunction "-IN_6") (pintype "input"))
      (node (ref "U2") (pin "9") (pinfunction "-IN_9") (pintype "input"))
      (node (ref "U4") (pin "13") (pinfunction "-IN_13") (pintype "input"))
    )
    (net (code "24") (name "LEDS_SCK") (class "Default")
      (node (ref "IC1") (pin "3") (pinfunction "SCLK_3") (pintype "bidirectional"))
      (node (ref "U1") (pin "26") (pinfunction "PB3_26") (pintype "bidirectional"))
    )
    (net (code "25") (name "LEDS_SIN") (class "Default")
      (node (ref "IC1") (pin "2") (pinfunction "SIN_2") (pintype "bidirectional"))
      (node (ref "U1") (pin "28") (pinfunction "PB5_28") (pintype "bidirectional"))
    )
    (net (code "26") (name "Net-(C13-Pad1)") (class "Default")
      (node (ref "C13") (pin "1") (pinfunction "1_1") (pintype "passive"))
      (node (ref "L3") (pin "1") (pinfunction "1_1") (pintype "passive"))
    )
    (net (code "27") (name "Net-(C23-Pad1)") (class "Default")
      (node (ref "C23") (pin "1") (pinfunction "1_1") (pintype "passive"))
      (node (ref "C50") (pin "2") (pinfunction "2_2") (pintype "passive"))
    )
    (net (code "28") (name "Net-(C34-Pad2)") (class "Default")
      (node (ref "C34") (pin "2") (pinfunction "2_2") (pintype "passive"))
      (node (ref "Q2") (pin "1") (pinfunction "1_1") (pintype "passive"))
      (node (ref "R22") (pin "2") (pinfunction "2_2") (pintype "passive"))
    )
    (net (code "29") (name "Net-(D1-PadC)") (class "Default")
      (node (ref "D1") (pin "C") (pinfunction "C_C") (pintype "passive"))
      (node (ref "Q7") (pin "B") (pinfunction "B_B") (pintype "passive"))
      (node (ref "R66") (pin "2") (pinfunction "2_2") (pintype "passive"))
      (node (ref "R69") (pin "2") (pinfunction "2_2") (pintype "passive"))
    )
    (net (code "30") (name "Net-(D2-PadC)") (class "Default")
      (node (ref "D2") (pin "C") (pinfunction "C_C") (pintype "passive"))
      (node (ref "Q5") (pin "B") (pinfunction "B_B") (pintype "passive"))
      (node (ref "R67") (pin "2") (pinfunction "2_2") (pintype "passive"))
      (node (ref "R70") (pin "2") (pinfunction "2_2") (pintype "passive"))
    )
    (net (code "31") (name "Net-(D3-PadC)") (class "Default")
      (node (ref "D3") (pin "C") (pinfunction "C_C") (pintype "passive"))
      (node (ref "L4") (pin "2") (pinfunction "2_2") (pintype "passive"))
      (node (ref "L5") (pin "2") (pinfunction "2_2") (pintype "passive"))
    )
    (net (code "32") (name "Net-(D4-PadA)") (class "Default")
      (node (ref "D4") (pin "A") (pinfunction "A_A") (pintype "passive"))
      (node (ref "L1") (pin "2") (pinfunction "2_2") (pintype "passive"))
    )
    (net (code "33") (name "Net-(D5-PadC)") (class "Default")
      (node (ref "D5") (pin "C") (pinfunction "C_C") (pintype "passive"))
      (node (ref "Q6") (pin "B") (pinfunction "B_B") (pintype "passive"))
      (node (ref "R68") (pin "2") (pinfunction "2_2") (pintype "passive"))
      (node (ref "R71") (pin "2") (pinfunction "2_2") (pintype "passive"))
    )
    (net (code "34") (name "Net-(IC1-IREF)") (class "Default")
      (node (ref "IC1") (pin "23") (pinfunction "IREF_23") (pintype "bidirectional"))
      (node (ref "R50") (pin "1") (pinfunction "1_1") (pintype "passive"))
    )
    (net (code "35") (name "Net-(IC1-OUT1)") (class "Default")
      (node (ref "IC1") (pin "6") (pinfunction "OUT1_6") (pintype "bidirectional"))
      (node (ref "R31") (pin "2") (pinfunction "2_2") (pintype "passive"))
    )
    (net (code "36") (name "Net-(IC1-OUT2)") (class "Default")
      (node (ref "IC1") (pin "7") (pinfunction "OUT2_7") (pintype "bidirectional"))
      (node (ref "MODE_C") (pin "RED_C") (pinfunction "RED_RED_C") (pintype "bidirectional"))
    )
    (net (code "37") (name "Net-(IC1-OUT3)") (class "Default")
      (node (ref "IC1") (pin "8") (pinfunction "OUT3_8") (pintype "bidirectional"))
      (node (ref "MODE_C") (pin "GREEN_C") (pinfunction "GRN_GREEN_C") (pintype "bidirectional"))
    )
    (net (code "38") (name "Net-(IC1-OUT4)") (class "Default")
      (node (ref "IC1") (pin "9") (pinfunction "OUT4_9") (pintype "bidirectional"))
      (node (ref "MODE_A") (pin "GREEN_C") (pinfunction "GRN_GREEN_C") (pintype "bidirectional"))
    )
    (net (code "39") (name "Net-(IC1-OUT5)") (class "Default")
      (node (ref "IC1") (pin "10") (pinfunction "OUT5_10") (pintype "bidirectional"))
      (node (ref "MODE_A") (pin "RED_C") (pinfunction "RED_RED_C") (pintype "bidirectional"))
    )
    (net (code "40") (name "Net-(IC1-OUT6)") (class "Default")
      (node (ref "IC1") (pin "11") (pinfunction "OUT6_11") (pintype "bidirectional"))
      (node (ref "MODE_B") (pin "GREEN_C") (pinfunction "GRN_GREEN_C") (pintype "bidirectional"))
    )
    (net (code "41") (name "Net-(IC1-OUT7)") (class "Default")
      (node (ref "IC1") (pin "12") (pinfunction "OUT7_12") (pintype "bidirectional"))
      (node (ref "MODE_B") (pin "RED_C") (pinfunction "RED_RED_C") (pintype "bidirectional"))
    )
    (net (code "42") (name "Net-(IC1-OUT8)") (class "Default")
      (node (ref "IC1") (pin "13") (pinfunction "OUT8_13") (pintype "bidirectional"))
      (node (ref "LED10") (pin "GREEN_C") (pinfunction "GRN_GREEN_C") (pintype "bidirectional"))
    )
    (net (code "43") (name "Net-(IC1-OUT9)") (class "Default")
      (node (ref "IC1") (pin "14") (pinfunction "OUT9_14") (pintype "bidirectional"))
      (node (ref "LED10") (pin "RED_C") (pinfunction "RED_RED_C") (pintype "bidirectional"))
    )
    (net (code "44") (name "Net-(IC1-OUT10)") (class "Default")
      (node (ref "IC1") (pin "15") (pinfunction "OUT10_15") (pintype "bidirectional"))
      (node (ref "LED11") (pin "RED_C") (pinfunction "RED_RED_C") (pintype "bidirectional"))
    )
    (net (code "45") (name "Net-(IC1-OUT11)") (class "Default")
      (node (ref "IC1") (pin "16") (pinfunction "OUT11_16") (pintype "bidirectional"))
      (node (ref "LED11") (pin "GREEN_C") (pinfunction "GRN_GREEN_C") (pintype "bidirectional"))
    )
    (net (code "46") (name "Net-(IC1-OUT12)") (class "Default")
      (node (ref "IC1") (pin "17") (pinfunction "OUT12_17") (pintype "bidirectional"))
      (node (ref "LED12") (pin "RED_C") (pinfunction "RED_RED_C") (pintype "bidirectional"))
    )
    (net (code "47") (name "Net-(IC1-OUT13)") (class "Default")
      (node (ref "IC1") (pin "18") (pinfunction "OUT13_18") (pintype "bidirectional"))
      (node (ref "LED12") (pin "GREEN_C") (pinfunction "GRN_GREEN_C") (pintype "bidirectional"))
    )
    (net (code "48") (name "Net-(IC1-OUT14)") (class "Default")
      (node (ref "IC1") (pin "19") (pinfunction "OUT14_19") (pintype "bidirectional"))
      (node (ref "R19") (pin "2") (pinfunction "2_2") (pintype "passive"))
    )
    (net (code "49") (name "Net-(IC1-OUT15)") (class "Default")
      (node (ref "IC1") (pin "20") (pinfunction "OUT15_20") (pintype "bidirectional"))
      (node (ref "R30") (pin "2") (pinfunction "2_2") (pintype "passive"))
    )
    (net (code "50") (name "Net-(IC1-VCC)") (class "Default")
      (node (ref "C7") (pin "1") (pinfunction "1_1") (pintype "passive"))
      (node (ref "C8") (pin "1") (pinfunction "1_1") (pintype "passive"))
      (node (ref "IC1") (pin "24") (pinfunction "VCC_24") (pintype "bidirectional"))
      (node (ref "L2") (pin "1") (pinfunction "1_1") (pintype "passive"))
    )
    (net (code "51") (name "Net-(IC2-VI)") (class "Default")
      (node (ref "C15") (pin "1") (pinfunction "1_1") (pintype "passive"))
      (node (ref "IC2") (pin "1") (pinfunction "VI_1") (pintype "input"))
      (node (ref "L3") (pin "2") (pinfunction "2_2") (pintype "passive"))
    )
    (net (code "52") (name "Net-(IC3A-X0)") (class "Default")
      (node (ref "IC3") (pin "13") (pinfunction "X0_13") (pintype "bidirectional"))
      (node (ref "POT_C") (pin "P$2") (pinfunction "S_P$2") (pintype "passive"))
    )
    (net (code "53") (name "Net-(IC3A-X1)") (class "Default")
      (node (ref "IC3") (pin "14") (pinfunction "X1_14") (pintype "bidirectional"))
      (node (ref "SLD_C") (pin "2") (pinfunction "S_2") (pintype "passive"))
    )
    (net (code "54") (name "Net-(IC3A-X2)") (class "Default")
      (node (ref "IC3") (pin "15") (pinfunction "X2_15") (pintype "bidirectional"))
      (node (ref "SLD_B") (pin "2") (pinfunction "S_2") (pintype "passive"))
    )
    (net (code "55") (name "Net-(IC3A-X3)") (class "Default")
      (node (ref "IC3") (pin "12") (pinfunction "X3_12") (pintype "bidirectional"))
      (node (ref "POT_A") (pin "P$2") (pinfunction "S_P$2") (pintype "passive"))
    )
    (net (code "56") (name "Net-(IC3A-X4)") (class "Default")
      (node (ref "IC3") (pin "1") (pinfunction "X4_1") (pintype "bidirectional"))
      (node (ref "SLD_A") (pin "2") (pinfunction "S_2") (pintype "passive"))
    )
    (net (code "57") (name "Net-(IC3A-X6)") (class "Default")
      (node (ref "IC3") (pin "2") (pinfunction "X6_2") (pintype "bidirectional"))
      (node (ref "POT_B") (pin "P$2") (pinfunction "S_P$2") (pintype "passive"))
    )
    (net (code "58") (name "Net-(IC7-VI)") (class "Default")
      (node (ref "C20") (pin "1") (pinfunction "1_1") (pintype "passive"))
      (node (ref "IC7") (pin "3") (pinfunction "VI_3") (pintype "input"))
      (node (ref "L4") (pin "1") (pinfunction "1_1") (pintype "passive"))
    )
    (net (code "59") (name "Net-(IC9A-+IN)") (class "Default")
      (node (ref "IC9") (pin "3") (pinfunction "+IN_3") (pintype "input"))
      (node (ref "R8") (pin "2") (pinfunction "2_2") (pintype "passive"))
      (node (ref "R9") (pin "1") (pinfunction "1_1") (pintype "passive"))
    )
    (net (code "60") (name "Net-(IC9A--IN)") (class "Default")
      (node (ref "IC9") (pin "2") (pinfunction "-IN_2") (pintype "input"))
      (node (ref "R10") (pin "1") (pinfunction "1_1") (pintype "passive"))
    )
    (net (code "61") (name "Net-(IC9A-OUT)") (class "Default")
      (node (ref "IC9") (pin "1") (pinfunction "OUT_1") (pintype "output"))
      (node (ref "R7") (pin "2") (pinfunction "2_2") (pintype "passive"))
      (node (ref "R8") (pin "1") (pinfunction "1_1") (pintype "passive"))
    )
    (net (code "62") (name "Net-(IC9B-+IN)") (class "Default")
      (node (ref "IC9") (pin "5") (pinfunction "+IN_5") (pintype "input"))
      (node (ref "R12") (pin "2") (pinfunction "2_2") (pintype "passive"))
      (node (ref "R13") (pin "1") (pinfunction "1_1") (pintype "passive"))
    )
    (net (code "63") (name "Net-(IC9B--IN)") (class "Default")
      (node (ref "IC9") (pin "6") (pinfunction "-IN_6") (pintype "input"))
      (node (ref "R14") (pin "1") (pinfunction "1_1") (pintype "passive"))
    )
    (net (code "64") (name "Net-(IC9B-OUT)") (class "Default")
      (node (ref "IC9") (pin "7") (pinfunction "OUT_7") (pintype "output"))
      (node (ref "R11") (pin "2") (pinfunction "2_2") (pintype "passive"))
      (node (ref "R12") (pin "1") (pinfunction "1_1") (pintype "passive"))
    )
    (net (code "65") (name "Net-(IC9C-+IN)") (class "Default")
      (node (ref "IC9") (pin "10") (pinfunction "+IN_10") (pintype "input"))
      (node (ref "R16") (pin "2") (pinfunction "2_2") (pintype "passive"))
      (node (ref "R17") (pin "1") (pinfunction "1_1") (pintype "passive"))
    )
    (net (code "66") (name "Net-(IC9C--IN)") (class "Default")
      (node (ref "IC9") (pin "9") (pinfunction "-IN_9") (pintype "input"))
      (node (ref "R20") (pin "1") (pinfunction "1_1") (pintype "passive"))
    )
    (net (code "67") (name "Net-(IC9C-OUT)") (class "Default")
      (node (ref "IC9") (pin "8") (pinfunction "OUT_8") (pintype "output"))
      (node (ref "R15") (pin "2") (pinfunction "2_2") (pintype "passive"))
      (node (ref "R16") (pin "1") (pinfunction "1_1") (pintype "passive"))
    )
    (net (code "68") (name "Net-(IC9D--IN)") (class "Default")
      (node (ref "IC9") (pin "13") (pinfunction "-IN_13") (pintype "input"))
      (node (ref "IC9") (pin "14") (pinfunction "OUT_14") (pintype "output"))
    )
    (net (code "69") (name "Net-(J1-3)") (class "Default")
      (node (ref "C27") (pin "1") (pinfunction "1_1") (pintype "passive"))
      (node (ref "J1") (pin "P3") (pinfunction "3_P3") (pintype "passive"))
      (node (ref "R6") (pin "2") (pinfunction "2_2") (pintype "passive"))
    )
    (net (code "70") (name "Net-(J2-3)") (class "Default")
      (node (ref "C29") (pin "1") (pinfunction "1_1") (pintype "passive"))
      (node (ref "J2") (pin "P3") (pinfunction "3_P3") (pintype "passive"))
      (node (ref "R51") (pin "2") (pinfunction "2_2") (pintype "passive"))
    )
    (net (code "71") (name "Net-(J3-3)") (class "Default")
      (node (ref "J3") (pin "P3") (pinfunction "3_P3") (pintype "passive"))
      (node (ref "R68") (pin "1") (pinfunction "1_1") (pintype "passive"))
    )
    (net (code "72") (name "Net-(J4-3)") (class "Default")
      (node (ref "J4") (pin "P3") (pinfunction "3_P3") (pintype "passive"))
      (node (ref "R67") (pin "1") (pinfunction "1_1") (pintype "passive"))
    )
    (net (code "73") (name "Net-(J5-3)") (class "Default")
      (node (ref "C25") (pin "1") (pinfunction "1_1") (pintype "passive"))
      (node (ref "J5") (pin "P3") (pinfunction "3_P3") (pintype "passive"))
      (node (ref "R4") (pin "2") (pinfunction "2_2") (pintype "passive"))
    )
    (net (code "74") (name "Net-(J6-3)") (class "Default")
      (node (ref "J6") (pin "P3") (pinfunction "3_P3") (pintype "passive"))
      (node (ref "R66") (pin "1") (pinfunction "1_1") (pintype "passive"))
    )
    (net (code "75") (name "Net-(J7-3)") (class "Default")
      (node (ref "J7") (pin "P3") (pinfunction "3_P3") (pintype "passive"))
      (node (ref "R35") (pin "1") (pinfunction "1_1") (pintype "passive"))
      (node (ref "R41") (pin "1") (pinfunction "1_1") (pintype "passive"))
    )
    (net (code "76") (name "Net-(J8-3)") (class "Default")
      (node (ref "J8") (pin "P3") (pinfunction "3_P3") (pintype "passive"))
      (node (ref "R32") (pin "1") (pinfunction "1_1") (pintype "passive"))
      (node (ref "R33") (pin "1") (pinfunction "1_1") (pintype "passive"))
    )
    (net (code "77") (name "Net-(J9-3)") (class "Default")
      (node (ref "J9") (pin "P3") (pinfunction "3_P3") (pintype "passive"))
      (node (ref "R36") (pin "1") (pinfunction "1_1") (pintype "passive"))
      (node (ref "R37") (pin "1") (pinfunction "1_1") (pintype "passive"))
    )
    (net (code "78") (name "Net-(J10-3)") (class "Default")
      (node (ref "J10") (pin "P3") (pinfunction "3_P3") (pintype "passive"))
      (node (ref "R7") (pin "1") (pinfunction "1_1") (pintype "passive"))
    )
    (net (code "79") (name "Net-(J11-3)") (class "Default")
      (node (ref "J11") (pin "P3") (pinfunction "3_P3") (pintype "passive"))
      (node (ref "R11") (pin "1") (pinfunction "1_1") (pintype "passive"))
    )
    (net (code "80") (name "Net-(J12-3)") (class "Default")
      (node (ref "J12") (pin "P3") (pinfunction "3_P3") (pintype "passive"))
      (node (ref "R15") (pin "1") (pinfunction "1_1") (pintype "passive"))
    )
    (net (code "81") (name "Net-(Q2B-2)") (class "Default")
      (node (ref "C35") (pin "2") (pinfunction "2_2") (pintype "passive"))
      (node (ref "Q2") (pin "3") (pinfunction "2_3") (pintype "passive"))
      (node (ref "R21") (pin "2") (pinfunction "2_2") (pintype "passive"))
    )
    (net (code "82") (name "Net-(SLD_AA-C)") (class "Default")
      (node (ref "R19") (pin "1") (pinfunction "1_1") (pintype "passive"))
      (node (ref "SLD_A") (pin "E") (pinfunction "C_E") (pintype "passive"))
    )
    (net (code "83") (name "Net-(SLD_BA-C)") (class "Default")
      (node (ref "R30") (pin "1") (pinfunction "1_1") (pintype "passive"))
      (node (ref "SLD_B") (pin "E") (pinfunction "C_E") (pintype "passive"))
    )
    (net (code "84") (name "Net-(SLD_CA-C)") (class "Default")
      (node (ref "R31") (pin "1") (pinfunction "1_1") (pintype "passive"))
      (node (ref "SLD_C") (pin "E") (pinfunction "C_E") (pintype "passive"))
    )
    (net (code "85") (name "Net-(U1-PF0{slash}OSC_IN)") (class "Default")
      (node (ref "R21") (pin "1") (pinfunction "1_1") (pintype "passive"))
      (node (ref "U1") (pin "2") (pinfunction "PF0/OSC_IN_2") (pintype "bidirectional"))
    )
    (net (code "86") (name "Net-(U1-PF1{slash}OSC_OUT)") (class "Default")
      (node (ref "R22") (pin "1") (pinfunction "1_1") (pintype "passive"))
      (node (ref "U1") (pin "3") (pinfunction "PF1/OSC_OUT_3") (pintype "bidirectional"))
    )
    (net (code "87") (name "Net-(U2A-+IN)") (class "Default")
      (node (ref "C12") (pin "1") (pinfunction "1_1") (pintype "passive"))
      (node (ref "R29") (pin "1") (pinfunction "1_1") (pintype "passive"))
      (node (ref "R4") (pin "1") (pinfunction "1_1") (pintype "passive"))
      (node (ref "R5") (pin "2") (pinfunction "2_2") (pintype "passive"))
      (node (ref "U2") (pin "3") (pinfunction "+IN_3") (pintype "input"))
    )
    (net (code "88") (name "Net-(U2B-+IN)") (class "Default")
      (node (ref "C26") (pin "1") (pinfunction "1_1") (pintype "passive"))
      (node (ref "R26") (pin "2") (pinfunction "2_2") (pintype "passive"))
      (node (ref "R28") (pin "1") (pinfunction "1_1") (pintype "passive"))
      (node (ref "R6") (pin "1") (pinfunction "1_1") (pintype "passive"))
      (node (ref "U2") (pin "5") (pinfunction "+IN_5") (pintype "input"))
    )
    (net (code "89") (name "Net-(U2C-+IN)") (class "Default")
      (node (ref "C28") (pin "1") (pinfunction "1_1") (pintype "passive"))
      (node (ref "R51") (pin "1") (pinfunction "1_1") (pintype "passive"))
      (node (ref "R52") (pin "2") (pinfunction "2_2") (pintype "passive"))
      (node (ref "R53") (pin "1") (pinfunction "1_1") (pintype "passive"))
      (node (ref "U2") (pin "10") (pinfunction "+IN_10") (pintype "input"))
    )
    (net (code "90") (name "Net-(U2D-+IN)") (class "Default")
      (node (ref "U2") (pin "12") (pinfunction "+IN_12") (pintype "input"))
      (node (ref "U2") (pin "14") (pinfunction "OUT_14") (pintype "output"))
    )
    (net (code "91") (name "Net-(U4A-+IN)") (class "Default")
      (node (ref "C1") (pin "1") (pinfunction "1_1") (pintype "passive"))
      (node (ref "R41") (pin "2") (pinfunction "2_2") (pintype "passive"))
      (node (ref "R47") (pin "1") (pinfunction "1_1") (pintype "passive"))
      (node (ref "U4") (pin "3") (pinfunction "+IN_3") (pintype "input"))
    )
    (net (code "92") (name "Net-(U4A-OUT)") (class "Default")
      (node (ref "C1") (pin "2") (pinfunction "2_2") (pintype "passive"))
      (node (ref "R35") (pin "2") (pinfunction "2_2") (pintype "passive"))
      (node (ref "U4") (pin "1") (pinfunction "OUT_1") (pintype "output"))
    )
    (net (code "93") (name "Net-(U4B-+IN)") (class "Default")
      (node (ref "C2") (pin "1") (pinfunction "1_1") (pintype "passive"))
      (node (ref "R33") (pin "2") (pinfunction "2_2") (pintype "passive"))
      (node (ref "R34") (pin "1") (pinfunction "1_1") (pintype "passive"))
      (node (ref "U4") (pin "5") (pinfunction "+IN_5") (pintype "input"))
    )
    (net (code "94") (name "Net-(U4B-OUT)") (class "Default")
      (node (ref "C2") (pin "2") (pinfunction "2_2") (pintype "passive"))
      (node (ref "R32") (pin "2") (pinfunction "2_2") (pintype "passive"))
      (node (ref "U4") (pin "7") (pinfunction "OUT_7") (pintype "output"))
    )
    (net (code "95") (name "Net-(U4C-+IN)") (class "Default")
      (node (ref "C3") (pin "1") (pinfunction "1_1") (pintype "passive"))
      (node (ref "R37") (pin "2") (pinfunction "2_2") (pintype "passive"))
      (node (ref "R38") (pin "1") (pinfunction "1_1") (pintype "passive"))
      (node (ref "U4") (pin "10") (pinfunction "+IN_10") (pintype "input"))
    )
    (net (code "96") (name "Net-(U4C-OUT)") (class "Default")
      (node (ref "C3") (pin "2") (pinfunction "2_2") (pintype "passive"))
      (node (ref "R36") (pin "2") (pinfunction "2_2") (pintype "passive"))
      (node (ref "U4") (pin "8") (pinfunction "OUT_8") (pintype "output"))
    )
    (net (code "97") (name "Net-(U4D-+IN)") (class "Default")
      (node (ref "U4") (pin "12") (pinfunction "+IN_12") (pintype "input"))
      (node (ref "U4") (pin "14") (pinfunction "OUT_14") (pintype "output"))
    )
    (net (code "98") (name "POTS_ADDR_A") (class "Default")
      (node (ref "IC3") (pin "11") (pinfunction "A_11") (pintype "input"))
      (node (ref "U1") (pin "13") (pinfunction "PA7_13") (pintype "bidirectional"))
    )
    (net (code "99") (name "POTS_ADDR_B") (class "Default")
      (node (ref "IC3") (pin "10") (pinfunction "B_10") (pintype "input"))
      (node (ref "U1") (pin "18") (pinfunction "PA8_18") (pintype "bidirectional"))
    )
    (net (code "100") (name "POTS_ADDR_C") (class "Default")
      (node (ref "IC3") (pin "9") (pinfunction "C_9") (pintype "input"))
      (node (ref "U1") (pin "19") (pinfunction "PA9_19") (pintype "bidirectional"))
    )
    (net (code "101") (name "RESET") (class "Default")
      (node (ref "C36") (pin "1") (pinfunction "1_1") (pintype "passive"))
      (node (ref "JP6") (pin "4") (pinfunction "4_4") (pintype "passive"))
      (node (ref "R18") (pin "2") (pinfunction "2_2") (pintype "passive"))
      (node (ref "U1") (pin "4") (pinfunction "NRST_4") (pintype "bidirectional"))
    )
    (net (code "102") (name "SWCLK") (class "Default")
      (node (ref "JP6") (pin "3") (pinfunction "3_3") (pintype "passive"))
      (node (ref "U1") (pin "24") (pinfunction "PA14_24") (pintype "bidirectional"))
    )
    (net (code "103") (name "SWDIO") (class "Default")
      (node (ref "JP6") (pin "2") (pinfunction "2_2") (pintype "passive"))
      (node (ref "U1") (pin "23") (pinfunction "PA13_23") (pintype "bidirectional"))
    )
    (net (code "104") (name "SW_MODE_A") (class "Default")
      (node (ref "SW_A") (pin "3") (pinfunction "3_3") (pintype "passive"))
      (node (ref "SW_A") (pin "4") (pinfunction "4_4") (pintype "passive"))
      (node (ref "U1") (pin "27") (pinfunction "PB4_27") (pintype "bidirectional"))
    )
    (net (code "105") (name "SW_MODE_B") (class "Default")
      (node (ref "SW_B") (pin "3") (pinfunction "3_3") (pintype "passive"))
      (node (ref "SW_B") (pin "4") (pinfunction "4_4") (pintype "passive"))
      (node (ref "U1") (pin "29") (pinfunction "PB6_29") (pintype "bidirectional"))
    )
    (net (code "106") (name "SW_MODE_C") (class "Default")
      (node (ref "SW_C") (pin "3") (pinfunction "3_3") (pintype "passive"))
      (node (ref "SW_C") (pin "4") (pinfunction "4_4") (pintype "passive"))
      (node (ref "U1") (pin "30") (pinfunction "PB7_30") (pintype "bidirectional"))
    )
    (net (code "107") (name "VCC") (class "Default")
      (node (ref "C14") (pin "1") (pinfunction "1_1") (pintype "passive"))
      (node (ref "C21") (pin "1") (pinfunction "1_1") (pintype "passive"))
      (node (ref "C4") (pin "1") (pinfunction "1_1") (pintype "passive"))
      (node (ref "C50") (pin "1") (pinfunction "1_1") (pintype "passive"))
      (node (ref "IC9") (pin "4") (pinfunction "V+_4") (pintype "power_in"))
      (node (ref "L5") (pin "1") (pinfunction "1_1") (pintype "passive"))
      (node (ref "U4") (pin "4") (pinfunction "V+_4") (pintype "power_in"))
    )
    (net (code "108") (name "VEE") (class "Default")
      (node (ref "C16") (pin "2") (pinfunction "2_2") (pintype "passive"))
      (node (ref "C18") (pin "2") (pinfunction "2_2") (pintype "passive"))
      (node (ref "C23") (pin "2") (pinfunction "2_2") (pintype "passive"))
      (node (ref "L1") (pin "1") (pinfunction "1_1") (pintype "passive"))
      (node (ref "R1") (pin "1") (pinfunction "1_1") (pintype "passive"))
      (node (ref "U4") (pin "11") (pinfunction "V-_11") (pintype "power_in"))
    )
    (net (code "109") (name "VREF_BIAS") (class "Default")
      (node (ref "C22") (pin "+") (pinfunction "+_+") (pintype "passive"))
      (node (ref "U$1") (pin "2") (pinfunction "VOUT_2") (pintype "output"))
      (node (ref "U4") (pin "2") (pinfunction "-IN_2") (pintype "input"))
      (node (ref "U4") (pin "6") (pinfunction "-IN_6") (pintype "input"))
      (node (ref "U4") (pin "9") (pinfunction "-IN_9") (pintype "input"))
    )
    (net (code "110") (name "unconnected-(IC1-LAT-Pad4)") (class "Default")
      (node (ref "IC1") (pin "4") (pinfunction "LAT_4") (pintype "bidirectional"))
    )
    (net (code "111") (name "unconnected-(IC1-OUT0-Pad5)") (class "Default")
      (node (ref "IC1") (pin "5") (pinfunction "OUT0_5") (pintype "bidirectional"))
    )
    (net (code "112") (name "unconnected-(IC1-SOUT-Pad22)") (class "Default")
      (node (ref "IC1") (pin "22") (pinfunction "SOUT_22") (pintype "bidirectional"))
    )
    (net (code "113") (name "unconnected-(IC3A-X5-Pad5)") (class "Default")
      (node (ref "IC3") (pin "5") (pinfunction "X5_5") (pintype "bidirectional"))
    )
    (net (code "114") (name "unconnected-(IC3A-X7-Pad4)") (class "Default")
      (node (ref "IC3") (pin "4") (pinfunction "X7_4") (pintype "bidirectional"))
    )
    (net (code "115") (name "unconnected-(J7-2-PadP2)") (class "Default")
      (node (ref "J7") (pin "P2") (pinfunction "2_P2") (pintype "passive"))
    )
    (net (code "116") (name "unconnected-(J8-2-PadP2)") (class "Default")
      (node (ref "J8") (pin "P2") (pinfunction "2_P2") (pintype "passive"))
    )
    (net (code "117") (name "unconnected-(J9-2-PadP2)") (class "Default")
      (node (ref "J9") (pin "P2") (pinfunction "2_P2") (pintype "passive"))
    )
    (net (code "118") (name "unconnected-(J10-2-PadP2)") (class "Default")
      (node (ref "J10") (pin "P2") (pinfunction "2_P2") (pintype "passive"))
    )
    (net (code "119") (name "unconnected-(J11-2-PadP2)") (class "Default")
      (node (ref "J11") (pin "P2") (pinfunction "2_P2") (pintype "passive"))
    )
    (net (code "120") (name "unconnected-(J12-2-PadP2)") (class "Default")
      (node (ref "J12") (pin "P2") (pinfunction "2_P2") (pintype "passive"))
    )
  )
)
